# 5V_3_3V_Rail.net
KiCad netlist of a schematic drawn in EAGLE
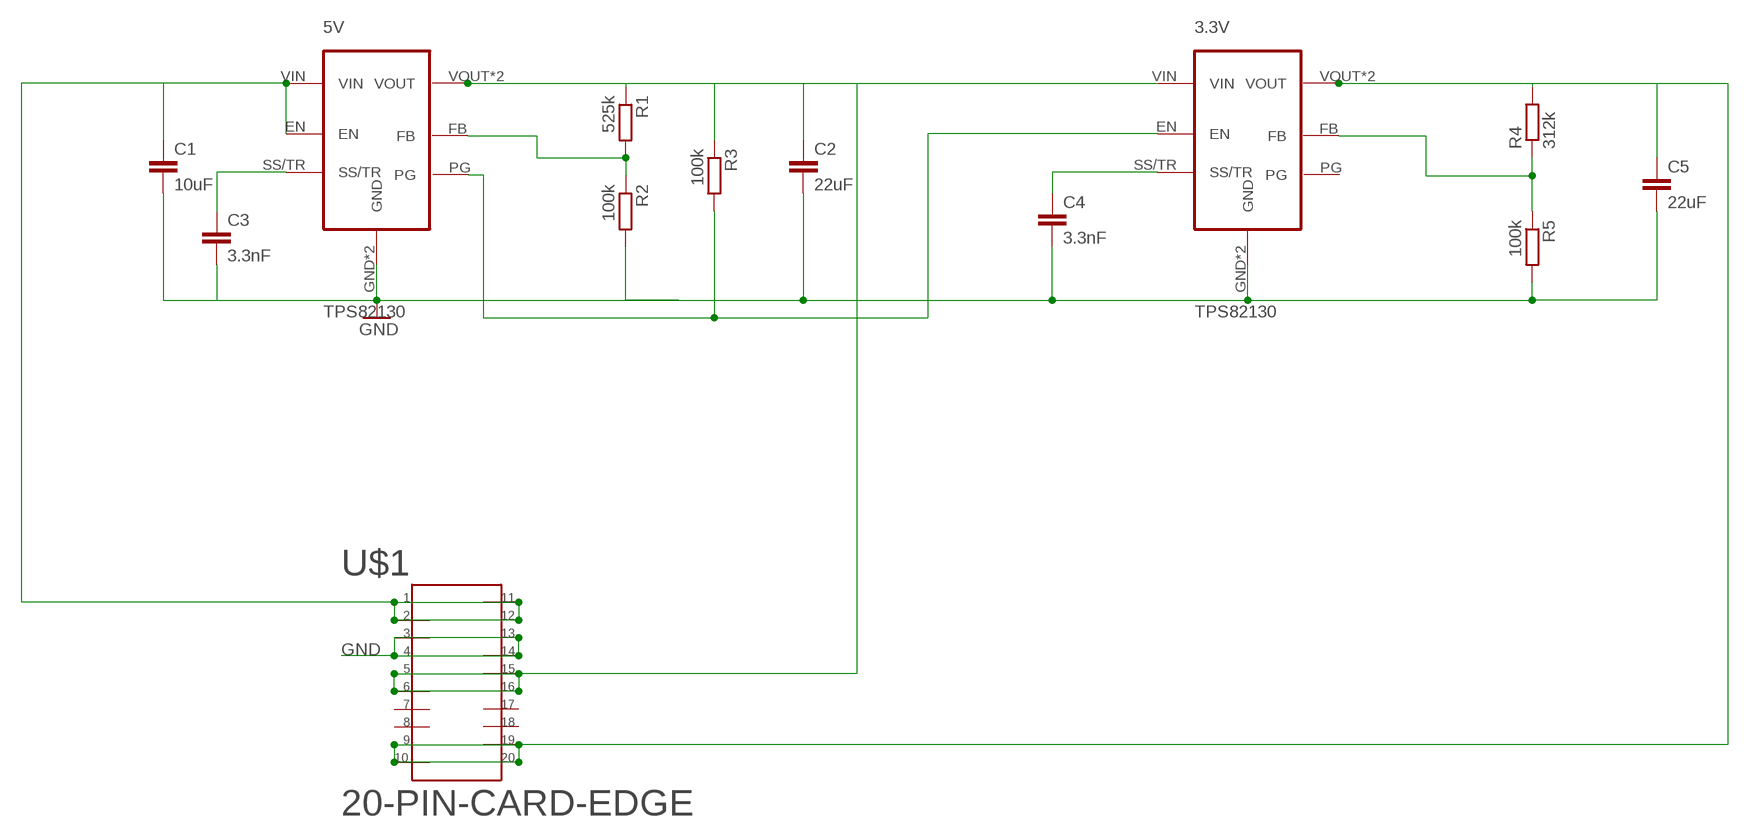
[diagram p0: schematic, sheet 1]

(export (version "E")
  (design (tool "Eeschema 10.0.6"))
  (components
    (comp (ref "3.3V")
      (value "TPS82130")
      (footprint "eagle-import:TPS82130")
      (libsource (lib "eagle-import") (part "TPS82130"))
    )
    (comp (ref "5V")
      (value "TPS82130")
      (footprint "eagle-import:TPS82130")
      (libsource (lib "eagle-import") (part "TPS82130"))
    )
    (comp (ref "C1")
      (value "10uF")
      (footprint "eagle-import:C0603")
      (libsource (lib "eagle-import") (part "C-EUC0603"))
    )
    (comp (ref "C2")
      (value "22uF")
      (footprint "eagle-import:C0603")
      (libsource (lib "eagle-import") (part "C-EUC0603"))
    )
    (comp (ref "C3")
      (value "3.3nF")
      (footprint "eagle-import:C0603")
      (libsource (lib "eagle-import") (part "C-EUC0603"))
    )
    (comp (ref "C4")
      (value "3.3nF")
      (footprint "eagle-import:C0603")
      (libsource (lib "eagle-import") (part "C-EUC0603"))
    )
    (comp (ref "C5")
      (value "22uF")
      (footprint "eagle-import:C0603")
      (libsource (lib "eagle-import") (part "C-EUC0603"))
    )
    (comp (ref "R1")
      (value "525k")
      (footprint "eagle-import:R0603")
      (libsource (lib "eagle-import") (part "R-EU_R0603"))
    )
    (comp (ref "R2")
      (value "100k")
      (footprint "eagle-import:R0603")
      (libsource (lib "eagle-import") (part "R-EU_R0603"))
    )
    (comp (ref "R3")
      (value "100k")
      (footprint "eagle-import:R0603")
      (libsource (lib "eagle-import") (part "R-EU_R0603"))
    )
    (comp (ref "R4")
      (value "312k")
      (footprint "eagle-import:R0603")
      (libsource (lib "eagle-import") (part "R-EU_R0603"))
    )
    (comp (ref "R5")
      (value "100k")
      (footprint "eagle-import:R0603")
      (libsource (lib "eagle-import") (part "R-EU_R0603"))
    )
    (comp (ref "U$1")
      (value "20-PIN-CARD-EDGE")
      (footprint "eagle-import:20-PIN-CARD-EDGE")
      (libsource (lib "eagle-import") (part "20-PIN-CARD-EDGE"))
    )
  )
  (nets
    (net (code "1") (name "GND") (class "Default")
      (node (ref "3.3V") (pin "GND") (pinfunction "GND_GND") (pintype "bidirectional"))
      (node (ref "3.3V") (pin "GND_PAD") (pinfunction "GND_GND_PAD") (pintype "bidirectional"))
      (node (ref "5V") (pin "GND") (pinfunction "GND_GND") (pintype "bidirectional"))
      (node (ref "5V") (pin "GND_PAD") (pinfunction "GND_GND_PAD") (pintype "bidirectional"))
      (node (ref "C1") (pin "2") (pinfunction "2_2") (pintype "passive"))
      (node (ref "C2") (pin "2") (pinfunction "2_2") (pintype "passive"))
      (node (ref "C3") (pin "2") (pinfunction "2_2") (pintype "passive"))
      (node (ref "C4") (pin "2") (pinfunction "2_2") (pintype "passive"))
      (node (ref "C5") (pin "2") (pinfunction "2_2") (pintype "passive"))
      (node (ref "R2") (pin "2") (pinfunction "2_2") (pintype "passive"))
      (node (ref "R5") (pin "2") (pinfunction "2_2") (pintype "passive"))
      (node (ref "U$1") (pin "P$13") (pinfunction "P$13_P$13") (pintype "bidirectional"))
      (node (ref "U$1") (pin "P$14") (pinfunction "P$14_P$14") (pintype "bidirectional"))
      (node (ref "U$1") (pin "P$3") (pinfunction "P$3_P$3") (pintype "bidirectional"))
      (node (ref "U$1") (pin "P$4") (pinfunction "P$4_P$4") (pintype "bidirectional"))
    )
    (net (code "2") (name "Net-(3.3V-PadEN)") (class "Default")
      (node (ref "3.3V") (pin "EN") (pinfunction "EN_EN") (pintype "bidirectional"))
      (node (ref "5V") (pin "PG") (pinfunction "PG_PG") (pintype "bidirectional"))
      (node (ref "R3") (pin "2") (pinfunction "2_2") (pintype "passive"))
    )
    (net (code "3") (name "Net-(3.3V-PadFB)") (class "Default")
      (node (ref "3.3V") (pin "FB") (pinfunction "FB_FB") (pintype "bidirectional"))
      (node (ref "R4") (pin "1") (pinfunction "1_1") (pintype "passive"))
      (node (ref "R5") (pin "1") (pinfunction "1_1") (pintype "passive"))
    )
    (net (code "4") (name "Net-(3.3V-PadSS{slash}TR)") (class "Default")
      (node (ref "3.3V") (pin "SS/TR") (pinfunction "SS/TR_SS/TR") (pintype "bidirectional"))
      (node (ref "C4") (pin "1") (pinfunction "1_1") (pintype "passive"))
    )
    (net (code "5") (name "Net-(3.3V-PadVIN)") (class "Default")
      (node (ref "3.3V") (pin "VIN") (pinfunction "VIN_VIN") (pintype "bidirectional"))
      (node (ref "5V") (pin "VOUT") (pinfunction "VOUT_VOUT") (pintype "bidirectional"))
      (node (ref "5V") (pin "VOUT_2") (pinfunction "VOUT_VOUT_2") (pintype "bidirectional"))
      (node (ref "C2") (pin "1") (pinfunction "1_1") (pintype "passive"))
      (node (ref "R1") (pin "1") (pinfunction "1_1") (pintype "passive"))
      (node (ref "R3") (pin "1") (pinfunction "1_1") (pintype "passive"))
      (node (ref "U$1") (pin "P$15") (pinfunction "P$15_P$15") (pintype "bidirectional"))
      (node (ref "U$1") (pin "P$16") (pinfunction "P$16_P$16") (pintype "bidirectional"))
      (node (ref "U$1") (pin "P$5") (pinfunction "P$5_P$5") (pintype "bidirectional"))
      (node (ref "U$1") (pin "P$6") (pinfunction "P$6_P$6") (pintype "bidirectional"))
    )
    (net (code "6") (name "Net-(3.3V-PadVOUT)") (class "Default")
      (node (ref "3.3V") (pin "VOUT") (pinfunction "VOUT_VOUT") (pintype "bidirectional"))
      (node (ref "3.3V") (pin "VOUT_2") (pinfunction "VOUT_VOUT_2") (pintype "bidirectional"))
      (node (ref "C5") (pin "1") (pinfunction "1_1") (pintype "passive"))
      (node (ref "R4") (pin "2") (pinfunction "2_2") (pintype "passive"))
      (node (ref "U$1") (pin "P$10") (pinfunction "P$10_P$10") (pintype "bidirectional"))
      (node (ref "U$1") (pin "P$19") (pinfunction "P$19_P$19") (pintype "bidirectional"))
      (node (ref "U$1") (pin "P$20") (pinfunction "P$20_P$20") (pintype "bidirectional"))
      (node (ref "U$1") (pin "P$9") (pinfunction "P$9_P$9") (pintype "bidirectional"))
    )
    (net (code "7") (name "Net-(5V-PadEN)") (class "Default")
      (node (ref "5V") (pin "EN") (pinfunction "EN_EN") (pintype "bidirectional"))
      (node (ref "5V") (pin "VIN") (pinfunction "VIN_VIN") (pintype "bidirectional"))
      (node (ref "C1") (pin "1") (pinfunction "1_1") (pintype "passive"))
      (node (ref "U$1") (pin "P$1") (pinfunction "P$1_P$1") (pintype "bidirectional"))
      (node (ref "U$1") (pin "P$11") (pinfunction "P$11_P$11") (pintype "bidirectional"))
      (node (ref "U$1") (pin "P$12") (pinfunction "P$12_P$12") (pintype "bidirectional"))
      (node (ref "U$1") (pin "P$2") (pinfunction "P$2_P$2") (pintype "bidirectional"))
    )
    (net (code "8") (name "Net-(5V-PadFB)") (class "Default")
      (node (ref "5V") (pin "FB") (pinfunction "FB_FB") (pintype "bidirectional"))
      (node (ref "R1") (pin "2") (pinfunction "2_2") (pintype "passive"))
      (node (ref "R2") (pin "1") (pinfunction "1_1") (pintype "passive"))
    )
    (net (code "9") (name "Net-(5V-PadSS{slash}TR)") (class "Default")
      (node (ref "5V") (pin "SS/TR") (pinfunction "SS/TR_SS/TR") (pintype "bidirectional"))
      (node (ref "C3") (pin "1") (pinfunction "1_1") (pintype "passive"))
    )
    (net (code "10") (name "unconnected-(3.3V-PadPG)") (class "Default")
      (node (ref "3.3V") (pin "PG") (pinfunction "PG_PG") (pintype "bidirectional"))
    )
    (net (code "11") (name "unconnected-(U$1-PadP$7)") (class "Default")
      (node (ref "U$1") (pin "P$7") (pinfunction "P$7_P$7") (pintype "bidirectional"))
    )
    (net (code "12") (name "unconnected-(U$1-PadP$8)") (class "Default")
      (node (ref "U$1") (pin "P$8") (pinfunction "P$8_P$8") (pintype "bidirectional"))
    )
    (net (code "13") (name "unconnected-(U$1-PadP$17)") (class "Default")
      (node (ref "U$1") (pin "P$17") (pinfunction "P$17_P$17") (pintype "bidirectional"))
    )
    (net (code "14") (name "unconnected-(U$1-PadP$18)") (class "Default")
      (node (ref "U$1") (pin "P$18") (pinfunction "P$18_P$18") (pintype "bidirectional"))
    )
  )
)
